# Interfaz_de_Memoria.net
KiCad netlist of a schematic drawn in Altium Designer
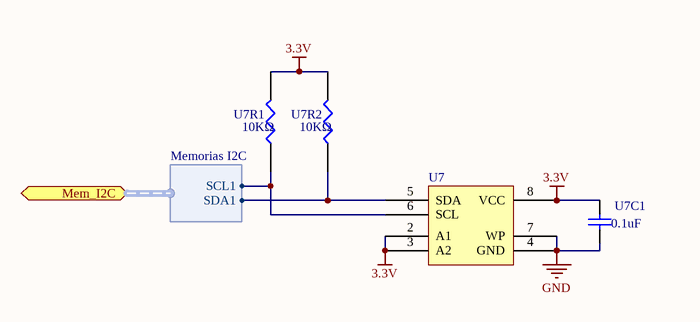
[diagram p0: Interfaz de Memoria.SchDoc]

(export (version "E")
  (design (tool "Eeschema 10.0.6"))
  (components
    (comp (ref "U7")
      (value "CAT24M01WI-GT3")
      (footprint "SO-G8/Y1.9")
      (description "IC EEPROM 1MBIT 1MHZ 8SOIC I2C")
      (fields (field (name "MANUFACTURER") "ON Semiconductor"))
      (libsource (lib "lib1") (part "AT24C1024BN-SH-B"))
    )
    (comp (ref "U7C1")
      (value "0.1uF")
      (footprint "0603 - CAP")
      (description "CAP CERAMIC 0.1UF, 25V, X7R, 0603")
      (fields
        (field (name "MANUFACTURER PART NUMBER") "CGJ3E2X7R1E104K080AA")
        (field (name "MANUFACTURER") "TDK Corporation")
      )
      (libsource (lib "*") (part "Cap"))
    )
    (comp (ref "U7R1")
      (value "10KΩ")
      (footprint "0805-RES")
      (description "10 kOhms ±5% 0.125W, 1/8W Chip Resistor 0805")
      (fields
        (field (name "MANUFACTURER PART NUMBER") "RC0805JR-0710KL")
        (field (name "MANUFACTURER") "Yageo")
      )
      (libsource (lib "*") (part "RES1"))
    )
    (comp (ref "U7R2")
      (value "10KΩ")
      (footprint "0805-RES")
      (description "10 kOhms ±5% 0.125W, 1/8W Chip Resistor 0805")
      (fields
        (field (name "MANUFACTURER PART NUMBER") "RC0805JR-0710KL")
        (field (name "MANUFACTURER") "Yageo")
      )
      (libsource (lib "*") (part "RES1"))
    )
  )
  (nets
    (net (code "4") (name "3.3V") (class "Default")
      (node (ref "U7") (pin "2") (pinfunction "A1_2") (pintype "passive"))
      (node (ref "U7") (pin "3") (pinfunction "A2_3") (pintype "passive"))
      (node (ref "U7") (pin "8") (pinfunction "VCC_8") (pintype "passive"))
      (node (ref "U7C1") (pin "2") (pinfunction "2_2") (pintype "passive"))
      (node (ref "U7R1") (pin "2") (pinfunction "2_2") (pintype "passive"))
      (node (ref "U7R2") (pin "2") (pinfunction "2_2") (pintype "passive"))
    )
    (net (code "5") (name "GND") (class "Default")
      (node (ref "U7") (pin "4") (pinfunction "GND_4") (pintype "passive"))
      (node (ref "U7") (pin "7") (pinfunction "WP_7") (pintype "passive"))
      (node (ref "U7C1") (pin "1") (pinfunction "1_1") (pintype "passive"))
    )
    (net (code "6") (name "Net-(U7-SCL)") (class "Default")
      (node (ref "U7") (pin "6") (pinfunction "SCL_6") (pintype "passive"))
      (node (ref "U7R1") (pin "1") (pinfunction "1_1") (pintype "passive"))
    )
    (net (code "7") (name "Net-(U7-SDA)") (class "Default")
      (node (ref "U7") (pin "5") (pinfunction "SDA_5") (pintype "passive"))
      (node (ref "U7R2") (pin "1") (pinfunction "1_1") (pintype "passive"))
    )
    (net (code "8") (name "unconnected-(U7-NC-Pad1)") (class "Default")
      (node (ref "U7") (pin "1") (pinfunction "NC_1") (pintype "passive"))
    )
  )
)
